# sound-op-switch.net
KiCad netlist of a schematic drawn in EAGLE
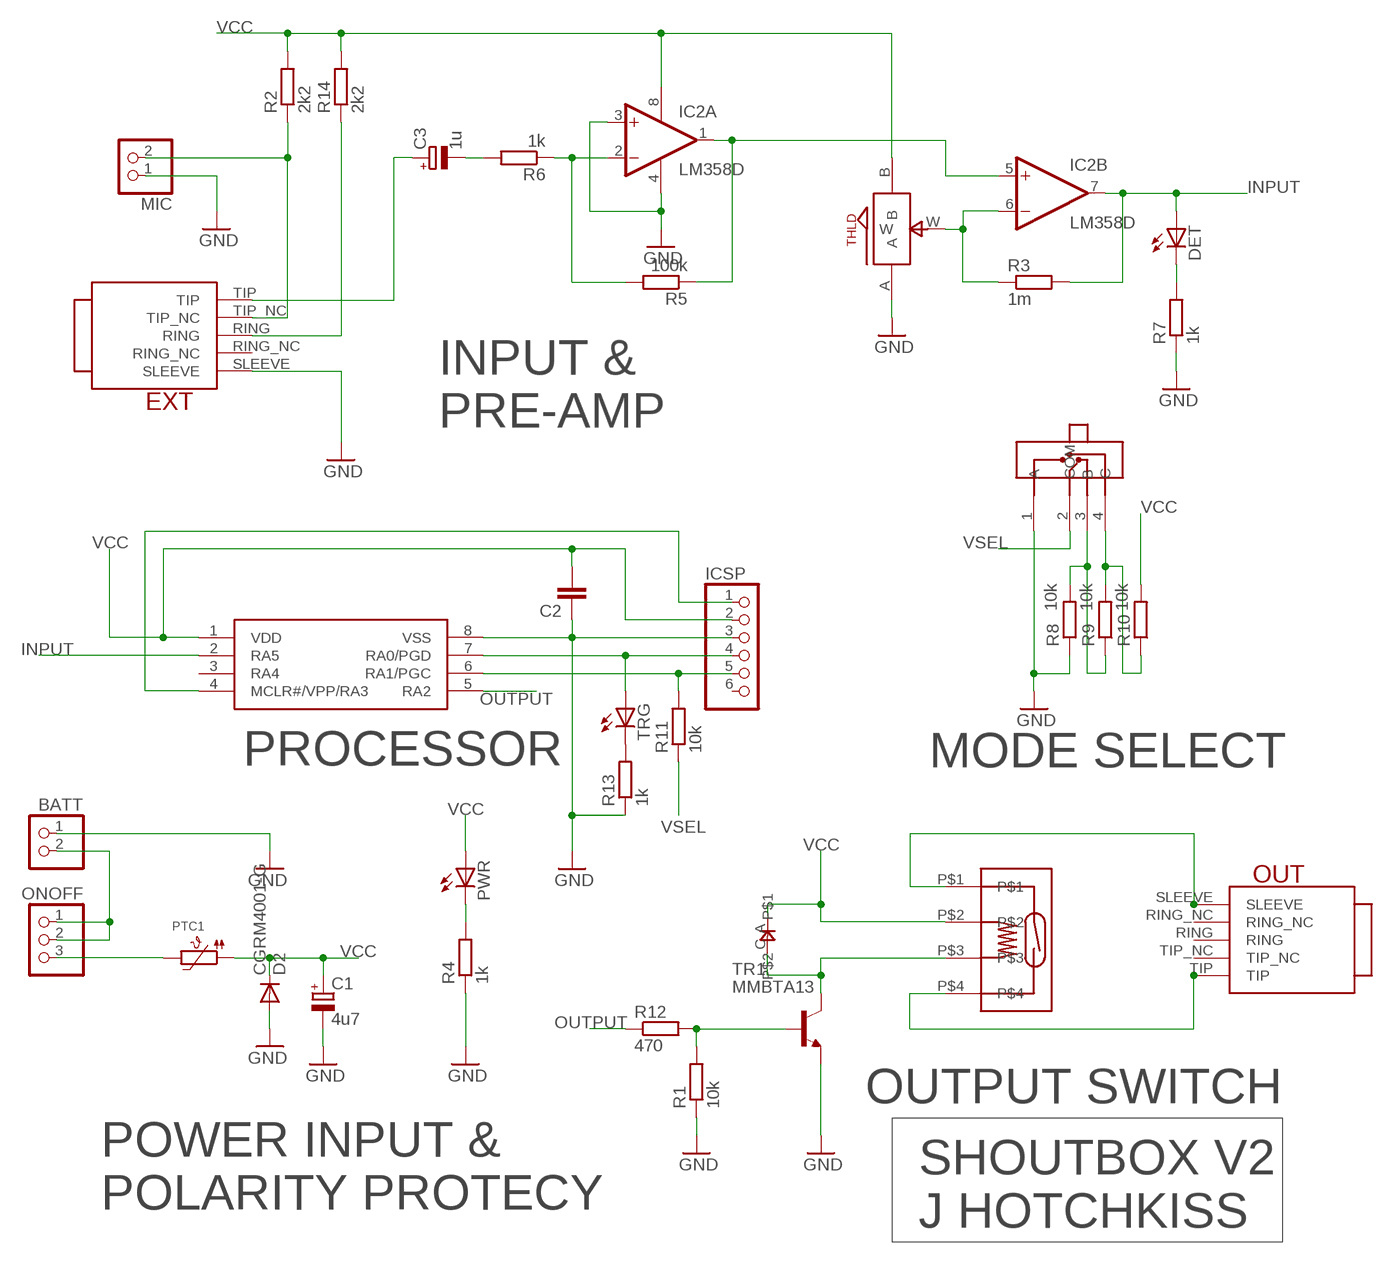
[diagram p0: schematic, sheet 1]

(export (version "E")
  (design (tool "Eeschema 10.0.6"))
  (components
    (comp (ref "BATT")
      (value "PINHD-1X2")
      (footprint "eagle-import:1X02")
      (libsource (lib "eagle-import") (part "PINHD-1X2"))
    )
    (comp (ref "C1")
      (value "4u7")
      (footprint "eagle-import:E2,5-6E")
      (libsource (lib "eagle-import") (part "CPOL-EUE2,5-6E"))
    )
    (comp (ref "C2")
      (value "C-EUC0805")
      (footprint "eagle-import:C0805")
      (libsource (lib "eagle-import") (part "C-EUC0805"))
    )
    (comp (ref "C3")
      (value "1u")
      (footprint "eagle-import:E2,5-6E")
      (libsource (lib "eagle-import") (part "CPOL-EUE2,5-6E"))
    )
    (comp (ref "D1")
      (value "0805DIODE")
      (footprint "eagle-import:0805DIODE")
      (libsource (lib "eagle-import") (part "0805DIODE"))
    )
    (comp (ref "D2")
      (value "CGRM4001-G")
      (footprint "eagle-import:SOD-123_MINI-SMA")
      (libsource (lib "eagle-import") (part "CGRM400-G1"))
    )
    (comp (ref "DET")
      (value "LED3MM")
      (footprint "eagle-import:LED3MM")
      (libsource (lib "eagle-import") (part "LED3MM"))
    )
    (comp (ref "EXT")
      (value "TRUCONNECTJACK")
      (footprint "eagle-import:TRUCONNECTJACK")
      (libsource (lib "eagle-import") (part "TRUCONNECTJACK"))
    )
    (comp (ref "IC1")
      (value "PIC12F1822")
      (footprint "eagle-import:DIL08")
      (libsource (lib "eagle-import") (part "PIC12F1822"))
    )
    (comp (ref "IC2")
      (value "LM358D")
      (footprint "eagle-import:SO08")
      (libsource (lib "eagle-import") (part "LM358D"))
    )
    (comp (ref "ICSP")
      (value "PINHD-1X6")
      (footprint "eagle-import:1X06")
      (libsource (lib "eagle-import") (part "PINHD-1X6"))
    )
    (comp (ref "MIC")
      (value "PINHD-1X2")
      (footprint "eagle-import:1X02")
      (libsource (lib "eagle-import") (part "PINHD-1X2"))
    )
    (comp (ref "ONOFF")
      (value "PINHD-1X3")
      (footprint "eagle-import:1X03")
      (libsource (lib "eagle-import") (part "PINHD-1X3"))
    )
    (comp (ref "OUT")
      (value "TRUCONNECTJACK")
      (footprint "eagle-import:TRUCONNECTJACK")
      (libsource (lib "eagle-import") (part "TRUCONNECTJACK"))
    )
    (comp (ref "PTC1")
      (value "PTC1206")
      (footprint "eagle-import:1206")
      (libsource (lib "eagle-import") (part "PTC1206"))
    )
    (comp (ref "PWR")
      (value "LED3MM")
      (footprint "eagle-import:LED3MM")
      (libsource (lib "eagle-import") (part "LED3MM"))
    )
    (comp (ref "R1")
      (value "10k")
      (footprint "eagle-import:R0805")
      (libsource (lib "eagle-import") (part "resistor_R-EU_R0805"))
    )
    (comp (ref "R2")
      (value "2k2")
      (footprint "eagle-import:R0805")
      (libsource (lib "eagle-import") (part "resistor_R-EU_R0805"))
    )
    (comp (ref "R3")
      (value "1m")
      (footprint "eagle-import:R0805")
      (libsource (lib "eagle-import") (part "resistor_R-EU_R0805"))
    )
    (comp (ref "R4")
      (value "1k")
      (footprint "eagle-import:R0805")
      (libsource (lib "eagle-import") (part "resistor_R-EU_R0805"))
    )
    (comp (ref "R5")
      (value "100k")
      (footprint "eagle-import:R0805")
      (libsource (lib "eagle-import") (part "R-EU_R0805"))
    )
    (comp (ref "R6")
      (value "1k")
      (footprint "eagle-import:R0805")
      (libsource (lib "eagle-import") (part "R-EU_R0805"))
    )
    (comp (ref "R7")
      (value "1k")
      (footprint "eagle-import:R0805")
      (libsource (lib "eagle-import") (part "resistor_R-EU_R0805"))
    )
    (comp (ref "R8")
      (value "10k")
      (footprint "eagle-import:R0805")
      (libsource (lib "eagle-import") (part "resistor_R-EU_R0805"))
    )
    (comp (ref "R9")
      (value "10k")
      (footprint "eagle-import:R0805")
      (libsource (lib "eagle-import") (part "resistor_R-EU_R0805"))
    )
    (comp (ref "R10")
      (value "10k")
      (footprint "eagle-import:R0805")
      (libsource (lib "eagle-import") (part "resistor_R-EU_R0805"))
    )
    (comp (ref "R11")
      (value "10k")
      (footprint "eagle-import:R0805")
      (libsource (lib "eagle-import") (part "resistor_R-EU_R0805"))
    )
    (comp (ref "R12")
      (value "470")
      (footprint "eagle-import:R0805")
      (libsource (lib "eagle-import") (part "resistor_R-EU_R0805"))
    )
    (comp (ref "R13")
      (value "1k")
      (footprint "eagle-import:R0805")
      (libsource (lib "eagle-import") (part "resistor_R-EU_R0805"))
    )
    (comp (ref "R14")
      (value "2k2")
      (footprint "eagle-import:R0805")
      (libsource (lib "eagle-import") (part "resistor_R-EU_R0805"))
    )
    (comp (ref "RLY1")
      (value "9007-REED-RELAY")
      (footprint "eagle-import:9007-REED-RELAY")
      (libsource (lib "eagle-import") (part "9007-REED-RELAY"))
    )
    (comp (ref "SEL")
      (value "SP4T-SLIDE")
      (footprint "eagle-import:SP3T-SLIDE")
      (libsource (lib "eagle-import") (part "SP4T-SLIDE"))
    )
    (comp (ref "THLD")
      (value "ALPS_POT_SMALL")
      (footprint "eagle-import:SMALL_ALPS_POT")
      (libsource (lib "eagle-import") (part "ALPS_POT_SMALL"))
    )
    (comp (ref "TR1")
      (value "MMBTA13")
      (footprint "eagle-import:SOT23-BEC")
      (libsource (lib "eagle-import") (part "-NPN-SOT23-BECMMBT3904LT1"))
    )
    (comp (ref "TRG")
      (value "LED3MM")
      (footprint "eagle-import:LED3MM")
      (libsource (lib "eagle-import") (part "LED3MM"))
    )
  )
  (nets
    (net (code "1") (name "/INPUT") (class "Default")
      (node (ref "DET") (pin "A") (pinfunction "A_A") (pintype "passive"))
      (node (ref "IC1") (pin "2") (pinfunction "RA5_2") (pintype "bidirectional"))
      (node (ref "IC2") (pin "7") (pinfunction "OUT_7") (pintype "output"))
      (node (ref "R3") (pin "2") (pinfunction "2_2") (pintype "passive"))
    )
    (net (code "2") (name "/OUTPUT") (class "Default")
      (node (ref "IC1") (pin "5") (pinfunction "RA2_5") (pintype "bidirectional"))
      (node (ref "R12") (pin "1") (pinfunction "1_1") (pintype "passive"))
    )
    (net (code "3") (name "/VCC") (class "Default")
      (node (ref "C1") (pin "+") (pinfunction "+_+") (pintype "passive"))
      (node (ref "C2") (pin "2") (pinfunction "2_2") (pintype "passive"))
      (node (ref "D1") (pin "A") (pinfunction "P$2_A") (pintype "bidirectional"))
      (node (ref "D2") (pin "C") (pinfunction "C_C") (pintype "passive"))
      (node (ref "IC1") (pin "1") (pinfunction "VDD_1") (pintype "power_in"))
      (node (ref "IC2") (pin "8") (pinfunction "V+_8") (pintype "power_in"))
      (node (ref "ICSP") (pin "2") (pinfunction "2_2") (pintype "passive"))
      (node (ref "PTC1") (pin "1") (pinfunction "1_1") (pintype "passive"))
      (node (ref "PWR") (pin "A") (pinfunction "A_A") (pintype "passive"))
      (node (ref "R10") (pin "2") (pinfunction "2_2") (pintype "passive"))
      (node (ref "R14") (pin "2") (pinfunction "2_2") (pintype "passive"))
      (node (ref "R2") (pin "2") (pinfunction "2_2") (pintype "passive"))
      (node (ref "RLY1") (pin "P$2") (pinfunction "P$2_P$2") (pintype "bidirectional"))
      (node (ref "THLD") (pin "B") (pinfunction "B_B") (pintype "bidirectional"))
    )
    (net (code "4") (name "/VSEL") (class "Default")
      (node (ref "R11") (pin "1") (pinfunction "1_1") (pintype "passive"))
      (node (ref "SEL") (pin "2") (pinfunction "COM_2") (pintype "bidirectional"))
    )
    (net (code "5") (name "GND") (class "Default")
      (node (ref "BATT") (pin "1") (pinfunction "1_1") (pintype "passive"))
      (node (ref "C1") (pin "-") (pinfunction "-_-") (pintype "passive"))
      (node (ref "C2") (pin "1") (pinfunction "1_1") (pintype "passive"))
      (node (ref "D2") (pin "A") (pinfunction "A_A") (pintype "passive"))
      (node (ref "EXT") (pin "SLEEVE") (pinfunction "SLEEVE_SLEEVE") (pintype "bidirectional"))
      (node (ref "IC1") (pin "8") (pinfunction "VSS_8") (pintype "power_in"))
      (node (ref "IC2") (pin "3") (pinfunction "+IN_3") (pintype "input"))
      (node (ref "IC2") (pin "4") (pinfunction "V-_4") (pintype "power_in"))
      (node (ref "ICSP") (pin "3") (pinfunction "3_3") (pintype "passive"))
      (node (ref "MIC") (pin "1") (pinfunction "1_1") (pintype "passive"))
      (node (ref "R1") (pin "1") (pinfunction "1_1") (pintype "passive"))
      (node (ref "R13") (pin "1") (pinfunction "1_1") (pintype "passive"))
      (node (ref "R4") (pin "1") (pinfunction "1_1") (pintype "passive"))
      (node (ref "R7") (pin "1") (pinfunction "1_1") (pintype "passive"))
      (node (ref "R8") (pin "1") (pinfunction "1_1") (pintype "passive"))
      (node (ref "SEL") (pin "1") (pinfunction "A_1") (pintype "bidirectional"))
      (node (ref "THLD") (pin "A") (pinfunction "A_A") (pintype "bidirectional"))
      (node (ref "TR1") (pin "E") (pinfunction "E_E") (pintype "passive"))
    )
    (net (code "6") (name "Net-(BATT-Pad2)") (class "Default")
      (node (ref "BATT") (pin "2") (pinfunction "2_2") (pintype "passive"))
      (node (ref "ONOFF") (pin "1") (pinfunction "1_1") (pintype "passive"))
      (node (ref "ONOFF") (pin "2") (pinfunction "2_2") (pintype "passive"))
    )
    (net (code "7") (name "Net-(C3-Pad+)") (class "Default")
      (node (ref "C3") (pin "+") (pinfunction "+_+") (pintype "passive"))
      (node (ref "EXT") (pin "TIP") (pinfunction "TIP_TIP") (pintype "bidirectional"))
    )
    (net (code "8") (name "Net-(C3-Pad-)") (class "Default")
      (node (ref "C3") (pin "-") (pinfunction "-_-") (pintype "passive"))
      (node (ref "R6") (pin "2") (pinfunction "2_2") (pintype "passive"))
    )
    (net (code "9") (name "Net-(D1-P$1)") (class "Default")
      (node (ref "D1") (pin "C") (pinfunction "P$1_C") (pintype "bidirectional"))
      (node (ref "RLY1") (pin "P$3") (pinfunction "P$3_P$3") (pintype "bidirectional"))
      (node (ref "TR1") (pin "C") (pinfunction "C_C") (pintype "passive"))
    )
    (net (code "10") (name "Net-(DET-C)") (class "Default")
      (node (ref "DET") (pin "K") (pinfunction "C_K") (pintype "passive"))
      (node (ref "R7") (pin "2") (pinfunction "2_2") (pintype "passive"))
    )
    (net (code "11") (name "Net-(EXT-PadRING)") (class "Default")
      (node (ref "EXT") (pin "RING") (pinfunction "RING_RING") (pintype "bidirectional"))
      (node (ref "R14") (pin "1") (pinfunction "1_1") (pintype "passive"))
    )
    (net (code "12") (name "Net-(EXT-PadTIP_NC)") (class "Default")
      (node (ref "EXT") (pin "TIP_NC") (pinfunction "TIP_NC_TIP_NC") (pintype "bidirectional"))
      (node (ref "MIC") (pin "2") (pinfunction "2_2") (pintype "passive"))
      (node (ref "R2") (pin "1") (pinfunction "1_1") (pintype "passive"))
    )
    (net (code "13") (name "Net-(IC1-MCLR#{slash}VPP{slash}RA3)") (class "Default")
      (node (ref "IC1") (pin "4") (pinfunction "MCLR#/VPP/RA3_4") (pintype "bidirectional"))
      (node (ref "ICSP") (pin "1") (pinfunction "1_1") (pintype "passive"))
    )
    (net (code "14") (name "Net-(IC1-RA0{slash}PGD)") (class "Default")
      (node (ref "IC1") (pin "7") (pinfunction "RA0/PGD_7") (pintype "bidirectional"))
      (node (ref "ICSP") (pin "4") (pinfunction "4_4") (pintype "passive"))
      (node (ref "TRG") (pin "A") (pinfunction "A_A") (pintype "passive"))
    )
    (net (code "15") (name "Net-(IC1-RA1{slash}PGC)") (class "Default")
      (node (ref "IC1") (pin "6") (pinfunction "RA1/PGC_6") (pintype "bidirectional"))
      (node (ref "ICSP") (pin "5") (pinfunction "5_5") (pintype "passive"))
      (node (ref "R11") (pin "2") (pinfunction "2_2") (pintype "passive"))
    )
    (net (code "16") (name "Net-(IC2A--IN)") (class "Default")
      (node (ref "IC2") (pin "2") (pinfunction "-IN_2") (pintype "input"))
      (node (ref "R5") (pin "2") (pinfunction "2_2") (pintype "passive"))
      (node (ref "R6") (pin "1") (pinfunction "1_1") (pintype "passive"))
    )
    (net (code "17") (name "Net-(IC2A-OUT)") (class "Default")
      (node (ref "IC2") (pin "1") (pinfunction "OUT_1") (pintype "output"))
      (node (ref "IC2") (pin "5") (pinfunction "+IN_5") (pintype "input"))
      (node (ref "R5") (pin "1") (pinfunction "1_1") (pintype "passive"))
    )
    (net (code "18") (name "Net-(IC2B--IN)") (class "Default")
      (node (ref "IC2") (pin "6") (pinfunction "-IN_6") (pintype "input"))
      (node (ref "R3") (pin "1") (pinfunction "1_1") (pintype "passive"))
      (node (ref "THLD") (pin "W") (pinfunction "W_W") (pintype "bidirectional"))
    )
    (net (code "19") (name "Net-(ONOFF-Pad3)") (class "Default")
      (node (ref "ONOFF") (pin "3") (pinfunction "3_3") (pintype "passive"))
      (node (ref "PTC1") (pin "2") (pinfunction "2_2") (pintype "passive"))
    )
    (net (code "20") (name "Net-(OUT-PadSLEEVE)") (class "Default")
      (node (ref "OUT") (pin "SLEEVE") (pinfunction "SLEEVE_SLEEVE") (pintype "bidirectional"))
      (node (ref "RLY1") (pin "P$1") (pinfunction "P$1_P$1") (pintype "bidirectional"))
    )
    (net (code "21") (name "Net-(OUT-PadTIP)") (class "Default")
      (node (ref "OUT") (pin "TIP") (pinfunction "TIP_TIP") (pintype "bidirectional"))
      (node (ref "RLY1") (pin "P$4") (pinfunction "P$4_P$4") (pintype "bidirectional"))
    )
    (net (code "22") (name "Net-(PWR-C)") (class "Default")
      (node (ref "PWR") (pin "K") (pinfunction "C_K") (pintype "passive"))
      (node (ref "R4") (pin "2") (pinfunction "2_2") (pintype "passive"))
    )
    (net (code "23") (name "Net-(R1-Pad2)") (class "Default")
      (node (ref "R1") (pin "2") (pinfunction "2_2") (pintype "passive"))
      (node (ref "R12") (pin "2") (pinfunction "2_2") (pintype "passive"))
      (node (ref "TR1") (pin "B") (pinfunction "B_B") (pintype "passive"))
    )
    (net (code "24") (name "Net-(SEL-B)") (class "Default")
      (node (ref "R8") (pin "2") (pinfunction "2_2") (pintype "passive"))
      (node (ref "R9") (pin "1") (pinfunction "1_1") (pintype "passive"))
      (node (ref "SEL") (pin "3") (pinfunction "B_3") (pintype "bidirectional"))
    )
    (net (code "25") (name "Net-(SEL-C)") (class "Default")
      (node (ref "R10") (pin "1") (pinfunction "1_1") (pintype "passive"))
      (node (ref "R9") (pin "2") (pinfunction "2_2") (pintype "passive"))
      (node (ref "SEL") (pin "4") (pinfunction "C_4") (pintype "bidirectional"))
    )
    (net (code "26") (name "Net-(TRG-C)") (class "Default")
      (node (ref "R13") (pin "2") (pinfunction "2_2") (pintype "passive"))
      (node (ref "TRG") (pin "K") (pinfunction "C_K") (pintype "passive"))
    )
    (net (code "27") (name "unconnected-(EXT-PadRING_NC)") (class "Default")
      (node (ref "EXT") (pin "RING_NC") (pinfunction "RING_NC_RING_NC") (pintype "bidirectional"))
    )
    (net (code "28") (name "unconnected-(IC1-RA4-Pad3)") (class "Default")
      (node (ref "IC1") (pin "3") (pinfunction "RA4_3") (pintype "bidirectional"))
    )
    (net (code "29") (name "unconnected-(ICSP-Pad6)") (class "Default")
      (node (ref "ICSP") (pin "6") (pinfunction "6_6") (pintype "passive"))
    )
    (net (code "30") (name "unconnected-(OUT-PadRING)") (class "Default")
      (node (ref "OUT") (pin "RING") (pinfunction "RING_RING") (pintype "bidirectional"))
    )
    (net (code "31") (name "unconnected-(OUT-PadRING_NC)") (class "Default")
      (node (ref "OUT") (pin "RING_NC") (pinfunction "RING_NC_RING_NC") (pintype "bidirectional"))
    )
    (net (code "32") (name "unconnected-(OUT-PadTIP_NC)") (class "Default")
      (node (ref "OUT") (pin "TIP_NC") (pinfunction "TIP_NC_TIP_NC") (pintype "bidirectional"))
    )
  )
)
